# 4.net
KiCad netlist of a schematic drawn in Altium Designer
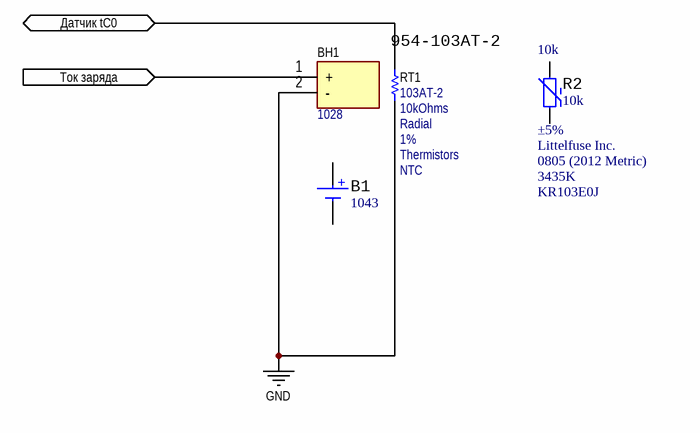
[diagram p0: Блок4.SchDoc]

(export (version "E")
  (design (tool "Eeschema 10.0.6"))
  (components
    (comp (ref "B1")
      (value "1043")
      (footprint "KEYSTONE 1043")
      (description "BATTERY HOLDER 18650 PC PIN")
      (fields (field (name "MANUFACTURER") "Keystone Electronics"))
      (libsource (lib "Celestial Altium Library - altium_library") (part "Keystone 1043"))
    )
    (comp (ref "BH1")
      (value "1028")
      (footprint "SamacSys:1028")
      (description "Undefined or Miscellaneous")
      (fields (field (name "MOUSER PART NUMBER") "534-1028"))
      (libsource (lib "*") (part "1028"))
    )
    (comp (ref "R2")
      (value "10k")
      (footprint "NTC 0805_2012")
      (description "THERMISTOR NTC 10KOHM 3435K 0805")
      (fields
        (field (name "PART NUMBER") "KR103E0J")
        (field (name "B25/85") "3435K")
        (field (name "MANUFACTURER") "Littelfuse Inc.")
        (field (name "PACKAGE / CASE") "0805 (2012 Metric)")
        (field (name "RESISTANCE IN OHMS @ 25°C") "10k")
        (field (name "RESISTANCE TOLERANCE") "±5%")
      )
      (libsource (lib "Celestial Altium Library - altium_library") (part "Thermistor"))
    )
    (comp (ref "RT1")
      (value "103AT-2")
      (footprint "SEMI-103AT-2_V")
      (description "Precision NTC Thermistor, 10 kOhm, +/- 1%, 10 mW, -50 to 110 degC, 2-Pin THD, RoHS, Bulk")
      (fields
        (field (name "MANUFACTURER") "Semitec")
        (field (name "RESISTANCE") "10kOhms")
        (field (name "TERMINATION STYLE") "Radial")
        (field (name "TOLERANCE") "1%")
        (field (name "PRODUCT CATEGORY") "Thermistors")
        (field (name "TYPE") "NTC")
        (field (name "SUPPLIER PART NUMBER 1") "954-103AT-2")
      )
      (libsource (lib "Altium Content Vault") (part "RES-THERMAL-2"))
    )
  )
  (nets
    (net (code "1") (name "/Датчик tC0") (class "Default")
      (node (ref "RT1") (pin "2") (pinfunction "2_2") (pintype "passive"))
    )
    (net (code "2") (name "/Ток заряда") (class "Default")
      (node (ref "BH1") (pin "1") (pinfunction "+_1") (pintype "passive"))
    )
    (net (code "3") (name "GND") (class "Default")
      (node (ref "BH1") (pin "2") (pinfunction "-_2") (pintype "passive"))
      (node (ref "RT1") (pin "1") (pinfunction "1_1") (pintype "passive"))
    )
    (net (code "4") (name "unconnected-(B1-+-Pad1)") (class "Default")
      (node (ref "B1") (pin "1") (pinfunction "+_1") (pintype "passive"))
    )
    (net (code "5") (name "unconnected-(B1---Pad2)") (class "Default")
      (node (ref "B1") (pin "2") (pinfunction "-_2") (pintype "passive"))
    )
    (net (code "6") (name "unconnected-(R2-Pad1)") (class "Default")
      (node (ref "R2") (pin "1") (pinfunction "1_1") (pintype "passive"))
    )
    (net (code "7") (name "unconnected-(R2-Pad2)") (class "Default")
      (node (ref "R2") (pin "2") (pinfunction "2_2") (pintype "passive"))
    )
  )
)
